# H03R0-J.net
KiCad netlist of a schematic drawn in EAGLE
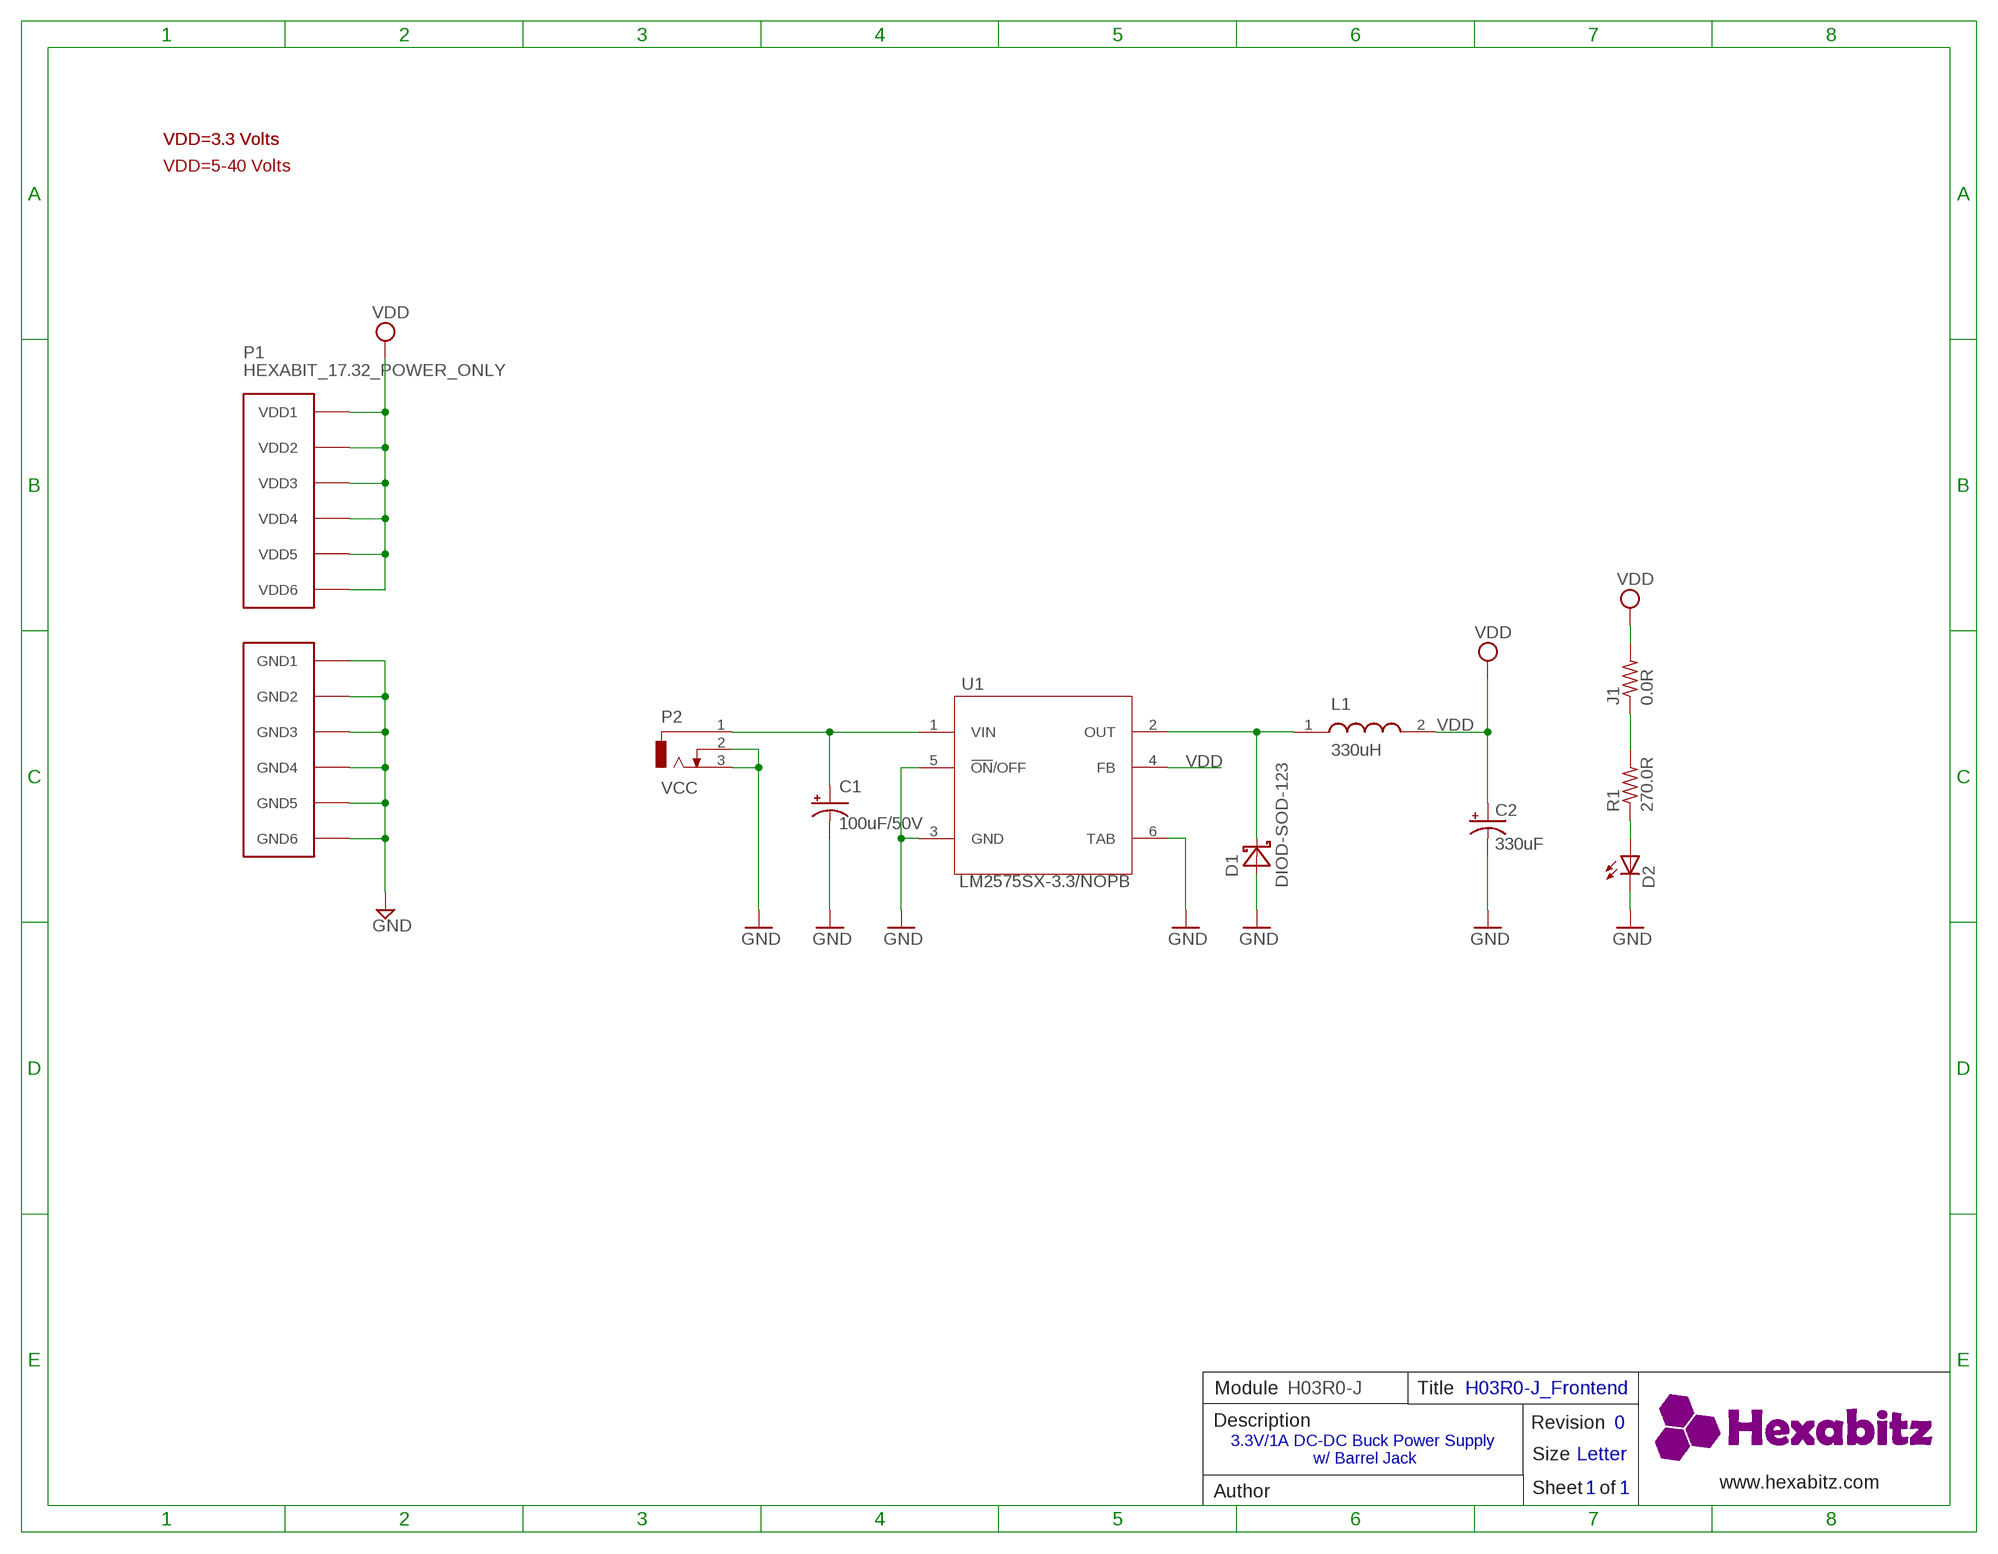
[diagram p0: schematic, sheet 1]

(export (version "E")
  (design (tool "Eeschema 10.0.6"))
  (components
    (comp (ref "C1")
      (value "100uF/50V")
      (footprint "eagle-import:E3,5-8")
      (fields
        (field (name "CAPACITANCE") "100F")
        (field (name "CPACITANCE_RATING") "±20%")
        (field (name "MFN") "Nichicon")
        (field (name "MPN") "UVR1H101MPD1TD")
        (field (name "OCTOPART_ID") "913e58b97f3b4ef9")
        (field (name "OCTOPART_URL") "http://octopart.com/uvr1h101mpd1td-nichicon-9292643")
        (field (name "VOLTAGE_RATING_DC") "50.0 V")
      )
      (libsource (lib "eagle-import") (part "CPOL-US"))
    )
    (comp (ref "C2")
      (value "330uF")
      (footprint "eagle-import:CAPPM7343X200N")
      (fields
        (field (name "MANUFACTURER_PART_NUMBER") "6TPC330MA")
        (field (name "MOUSER_PART_NUMBER") "667-6TPC330MA")
        (field (name "RS_PART_NUMBER") "1666900")
      )
      (libsource (lib "eagle-import") (part "AVX-E"))
    )
    (comp (ref "D1")
      (value "DIOD-SOD-123")
      (footprint "eagle-import:SOD123")
      (fields
        (field (name "CAPACITANCE") "1.1e-10 F")
        (field (name "CURRENT_RATING") "1.0 A")
        (field (name "MFN") "diodes")
        (field (name "MPN") "1N5819HW-7-F")
        (field (name "OCTOPART_ID") "e83e2130232537f9")
        (field (name "OCTOPART_URL") "https://octopart.com/1n5819hw-7-f-diodes+inc.-323197")
        (field (name "VOLTAGE_RATING_DC") "40.0 V")
      )
      (libsource (lib "eagle-import") (part "DIOD-SOD-123"))
    )
    (comp (ref "D2")
      (value "VLMS1300-GS08")
      (footprint "eagle-import:VLMS1300-GS08")
      (fields
        (field (name "MFN") "Vishay")
        (field (name "MPN") "VLMTG1300-GS08")
        (field (name "OCTOPART_URL") "http://octopart.com/vlmtg1300-gs08-vishay-21709202")
      )
      (libsource (lib "eagle-import") (part "VLMS1300-GS08"))
    )
    (comp (ref "J1")
      (value "0.0R")
      (footprint "eagle-import:R-0603")
      (fields
        (field (name "MFN") "Yageo")
        (field (name "MPN") "RC0603JR-070RL")
        (field (name "OCTOPART_URL") "https://octopart.com/crcw06030000z0eahp-vishay-44320230")
        (field (name "RESISTANCE") "0.0 Ω")
      )
      (libsource (lib "eagle-import") (part "R-0603"))
    )
    (comp (ref "L1")
      (value "330uH")
      (footprint "eagle-import:SRR1280-150M")
      (fields
        (field (name "MANUFACTURER_PART_NUMBER") "SRR1280-331K")
        (field (name "MOUSER_PART_NUMBER") "652-SRR1280-331K")
        (field (name "RS_PART_NUMBER") "1728540")
      )
      (libsource (lib "eagle-import") (part "SRR1280-331K"))
    )
    (comp (ref "P1")
      (value "HEXABIT_17.32_POWER_ONLY")
      (footprint "eagle-import:HEXABIT_17.32_POWER_ONLY")
      (libsource (lib "eagle-import") (part "HEXABIT_?_POWER_ONLY17.32"))
    )
    (comp (ref "P2")
      (value "VCC")
      (footprint "eagle-import:DCJ0202")
      (fields (field (name "MF") "CUI") (field (name "MPN") "PJ-202A"))
      (libsource (lib "eagle-import") (part "DCJ0202"))
    )
    (comp (ref "R1")
      (value "270.0R")
      (footprint "eagle-import:R-0603")
      (fields
        (field (name "MFN") "Yageo")
        (field (name "MPN") "RC0603FR-07270RL")
        (field (name "OCTOPART_URL") "https://octopart.com/crcw0603270rjnea-vishay-39784736")
        (field (name "RESISTANCE") "270.0 Ω")
        (field (name "TOLERANCE") "±5%")
      )
      (libsource (lib "eagle-import") (part "R-0603"))
    )
    (comp (ref "U1")
      (value "LM2575SX-3.3/NOPB")
      (footprint "eagle-import:TO170P1435X457-6N")
      (fields
        (field (name "DIGI-KEY_PART_NUMBER") "LM2575SX-3.3/NOPBCT-ND")
        (field (name "MF") "Texas Instruments")
      )
      (libsource (lib "eagle-import") (part "LM2575SX-3.3/NOPB"))
    )
  )
  (nets
    (net (code "1") (name "GND") (class "Default")
      (node (ref "C1") (pin "-") (pinfunction "-_-") (pintype "passive"))
      (node (ref "C2") (pin "2") (pinfunction "-_2") (pintype "passive"))
      (node (ref "D1") (pin "1") (pinfunction "A_1") (pintype "passive"))
      (node (ref "D2") (pin "C") (pinfunction "C_C") (pintype "passive"))
      (node (ref "P1") (pin "PAD_PD10") (pinfunction "GND4_PAD_PD10") (pintype "power_in"))
      (node (ref "P1") (pin "PAD_PD11") (pinfunction "GND5_PAD_PD11") (pintype "power_in"))
      (node (ref "P1") (pin "PAD_PD12") (pinfunction "GND6_PAD_PD12") (pintype "power_in"))
      (node (ref "P1") (pin "PAD_PD7") (pinfunction "GND1_PAD_PD7") (pintype "power_in"))
      (node (ref "P1") (pin "PAD_PD8") (pinfunction "GND2_PAD_PD8") (pintype "power_in"))
      (node (ref "P1") (pin "PAD_PD9") (pinfunction "GND3_PAD_PD9") (pintype "power_in"))
      (node (ref "P2") (pin "2") (pinfunction "2_2") (pintype "passive"))
      (node (ref "P2") (pin "3") (pinfunction "3_3") (pintype "passive"))
      (node (ref "U1") (pin "3") (pinfunction "GND_3") (pintype "passive"))
      (node (ref "U1") (pin "5") (pinfunction "ON/OFF_5") (pintype "input"))
      (node (ref "U1") (pin "6") (pinfunction "TAB_6") (pintype "passive"))
    )
    (net (code "2") (name "Net-(D1-C)") (class "Default")
      (node (ref "D1") (pin "2") (pinfunction "C_2") (pintype "passive"))
      (node (ref "L1") (pin "1") (pinfunction "1_1") (pintype "bidirectional"))
      (node (ref "U1") (pin "2") (pinfunction "OUT_2") (pintype "output"))
    )
    (net (code "3") (name "Net-(D2-PadA)") (class "Default")
      (node (ref "D2") (pin "A") (pinfunction "A_A") (pintype "passive"))
      (node (ref "R1") (pin "1") (pinfunction "1_1") (pintype "passive"))
    )
    (net (code "4") (name "Net-(J1-Pad1)") (class "Default")
      (node (ref "J1") (pin "1") (pinfunction "1_1") (pintype "passive"))
      (node (ref "R1") (pin "2") (pinfunction "2_2") (pintype "passive"))
    )
    (net (code "5") (name "Net-(U1-VIN)") (class "Default")
      (node (ref "C1") (pin "+") (pinfunction "+_+") (pintype "passive"))
      (node (ref "P2") (pin "1") (pinfunction "1_1") (pintype "passive"))
      (node (ref "U1") (pin "1") (pinfunction "VIN_1") (pintype "power_in"))
    )
    (net (code "6") (name "VDD") (class "Default")
      (node (ref "C2") (pin "1") (pinfunction "+_1") (pintype "passive"))
      (node (ref "J1") (pin "2") (pinfunction "2_2") (pintype "passive"))
      (node (ref "L1") (pin "2") (pinfunction "2_2") (pintype "bidirectional"))
      (node (ref "P1") (pin "PAD_PU10") (pinfunction "VDD4_PAD_PU10") (pintype "power_in"))
      (node (ref "P1") (pin "PAD_PU11") (pinfunction "VDD5_PAD_PU11") (pintype "power_in"))
      (node (ref "P1") (pin "PAD_PU12") (pinfunction "VDD6_PAD_PU12") (pintype "power_in"))
      (node (ref "P1") (pin "PAD_PU7") (pinfunction "VDD1_PAD_PU7") (pintype "power_in"))
      (node (ref "P1") (pin "PAD_PU8") (pinfunction "VDD2_PAD_PU8") (pintype "power_in"))
      (node (ref "P1") (pin "PAD_PU9") (pinfunction "VDD3_PAD_PU9") (pintype "power_in"))
      (node (ref "U1") (pin "4") (pinfunction "FB_4") (pintype "input"))
    )
  )
)
